# Fri3D_Air_2018_00.net
KiCad netlist of a schematic drawn in Altium Designer
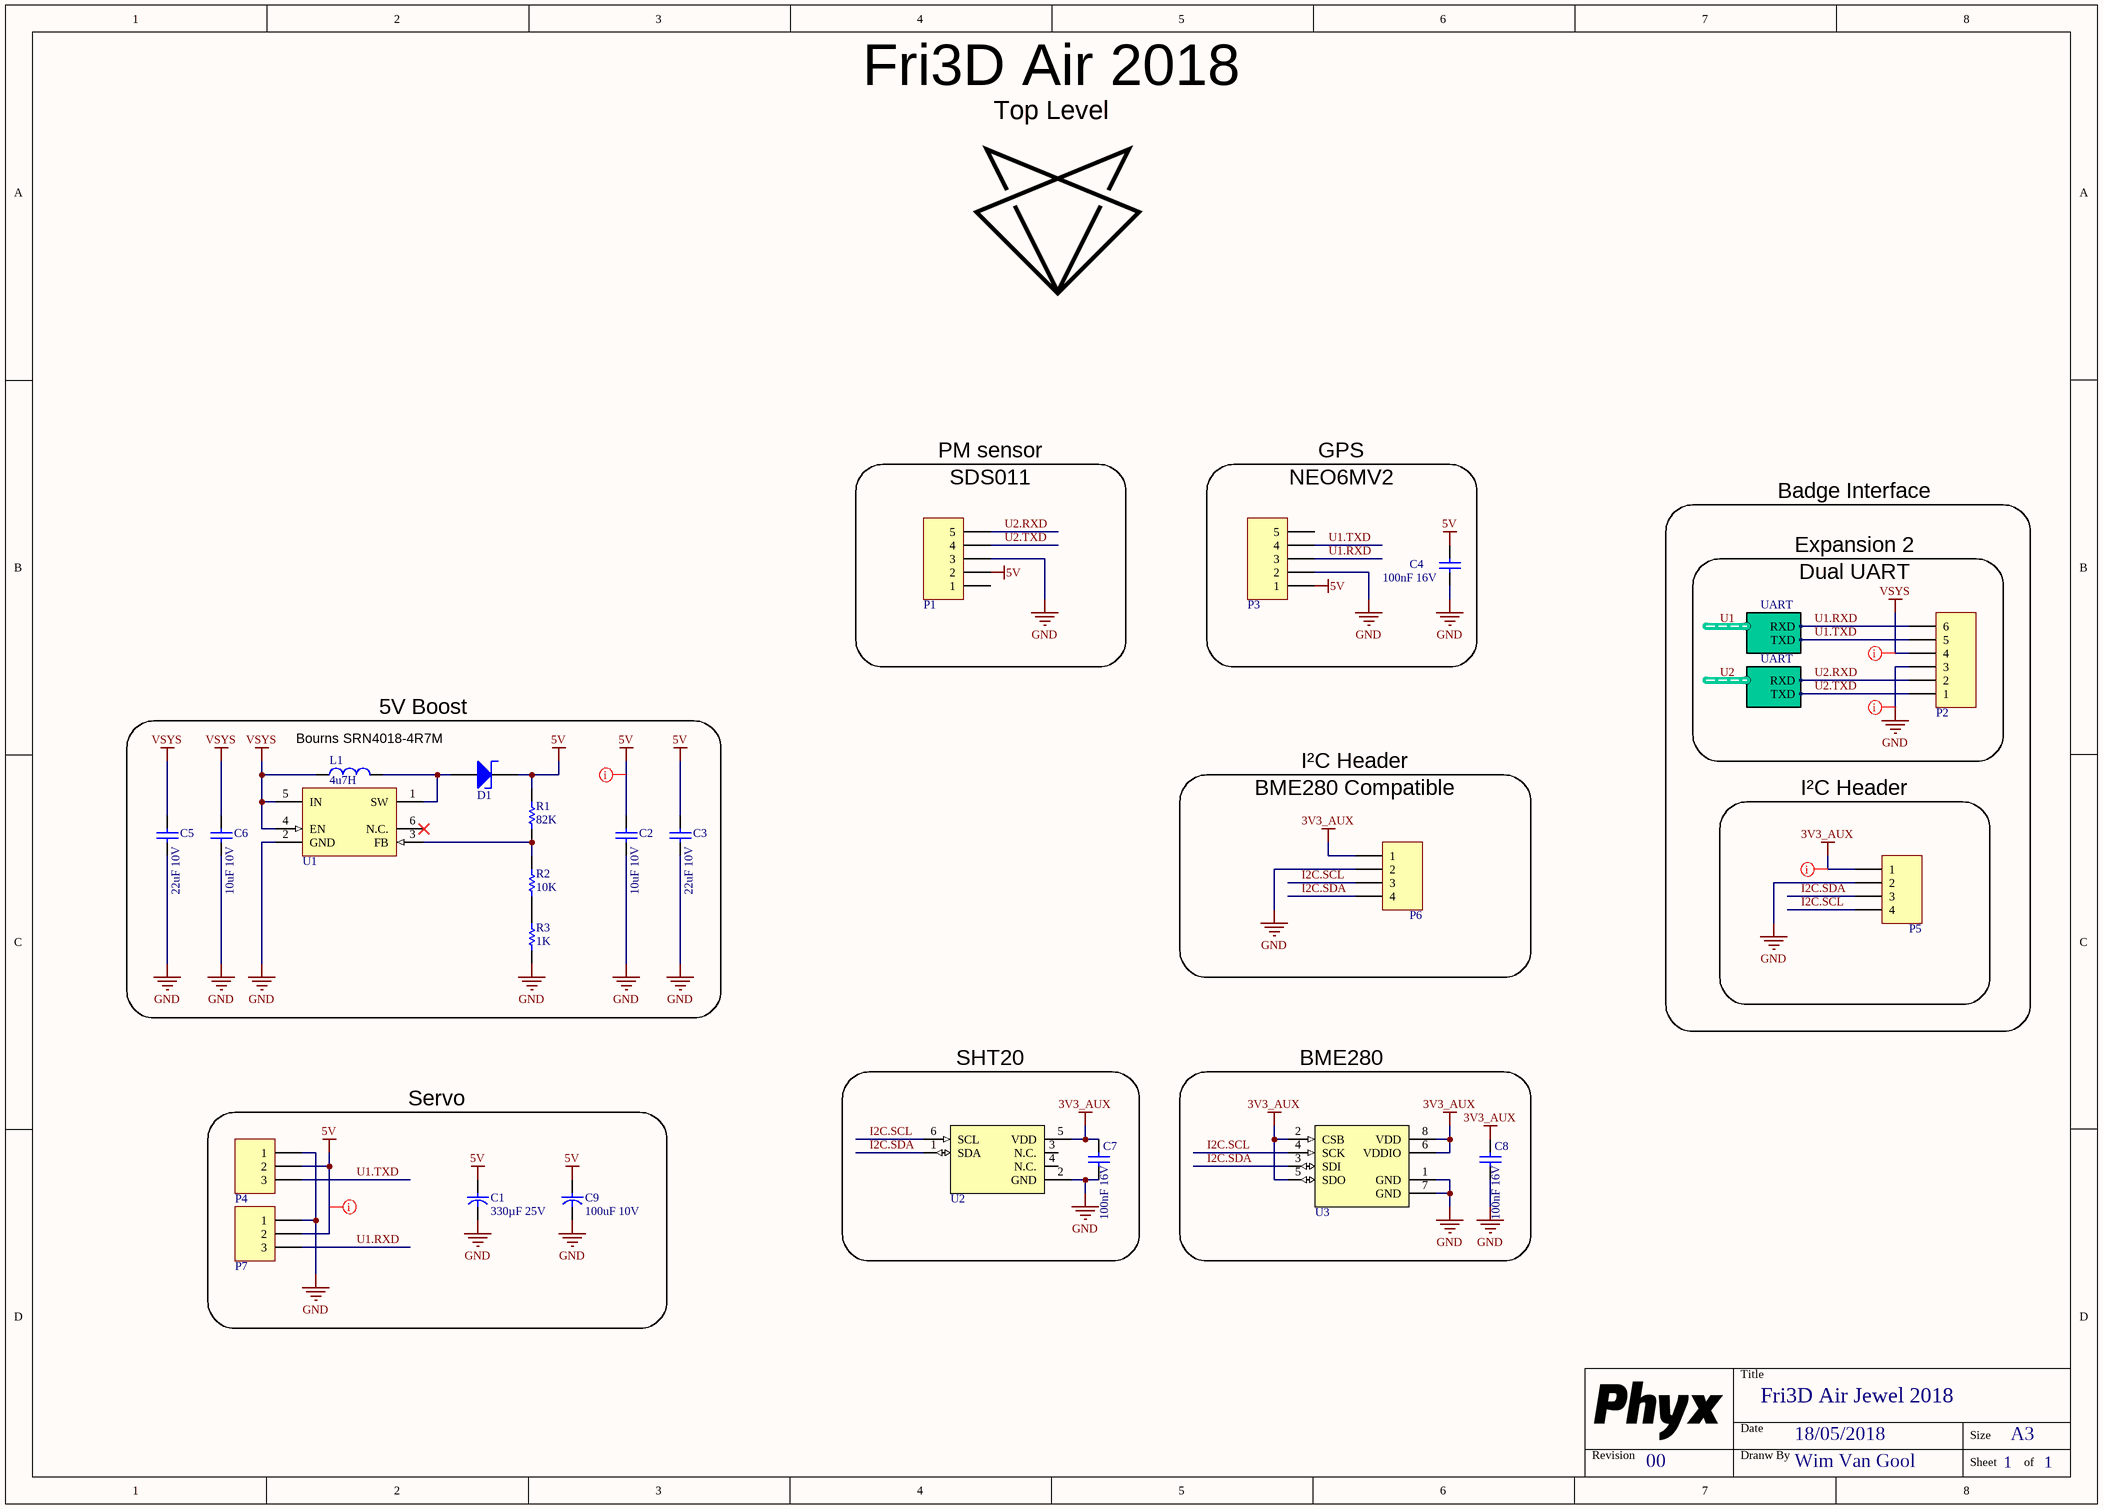
[diagram p0: Fri3D_Air_2018_00.SchDoc]

(export (version "E")
  (design (tool "Eeschema 10.0.6"))
  (components
    (comp (ref "C1")
      (value "330µF 25V")
      (footprint "C_8x15_3.5mm")
      (description "Capacitor electrolyt")
      (fields (field (name "Comment") "CAP_POL"))
      (libsource (lib "Phyx_Components") (part "CAP_POL"))
    )
    (comp (ref "C2")
      (value "10uF 10V")
      (footprint "C0805_N")
      (description "Capacitor Ceramic")
      (fields (field (name "Comment") "CAP_CERAMIC"))
      (libsource (lib "Phyx_Components") (part "CAP_CERAMIC"))
    )
    (comp (ref "C3")
      (value "22uF 10V")
      (footprint "C1210_N")
      (description "Capacitor Ceramic")
      (fields (field (name "Comment") "CAP_CERAMIC"))
      (libsource (lib "Phyx_Components") (part "CAP_CERAMIC"))
    )
    (comp (ref "C4")
      (value "100nF 16V")
      (footprint "C0603_N")
      (description "Capacitor Ceramic")
      (libsource (lib "Phyx_Components") (part "CAP_CERAMIC"))
    )
    (comp (ref "C5")
      (value "22uF 10V")
      (footprint "C1210_N")
      (description "Capacitor Ceramic")
      (fields (field (name "Comment") "CAP_CERAMIC"))
      (libsource (lib "Phyx_Components") (part "CAP_CERAMIC"))
    )
    (comp (ref "C6")
      (value "10uF 10V")
      (footprint "C0805_N")
      (description "Capacitor Ceramic")
      (fields (field (name "Comment") "CAP_CERAMIC"))
      (libsource (lib "Phyx_Components") (part "CAP_CERAMIC"))
    )
    (comp (ref "C7")
      (value "100nF 16V")
      (footprint "C0603_N")
      (description "Capacitor Ceramic")
      (libsource (lib "Phyx_Components") (part "CAP_CERAMIC"))
    )
    (comp (ref "C8")
      (value "100nF 16V")
      (footprint "C0603_N")
      (description "Capacitor Ceramic")
      (libsource (lib "Phyx_Components") (part "CAP_CERAMIC"))
    )
    (comp (ref "C9")
      (value "100uF 10V")
      (footprint "C_5x11_2mm")
      (description "Capacitor electrolyt")
      (fields (field (name "Comment") "CAP_POL"))
      (libsource (lib "Phyx_Components") (part "CAP_POL"))
    )
    (comp (ref "D1")
      (value "NTS260SFT1G  Schottky Rectifier, Single, 60 V, 2 A, SOD-123, 650 mV")
      (footprint "ON_SOD-123FL")
      (description "=Description")
      (libsource (lib "Phyx_Components") (part "Schottky_21"))
    )
    (comp (ref "L1")
      (value "4u7H")
      (footprint "SNL_SWPA4020")
      (fields (field (name "Comment") "SWPA4020S4R7MT"))
      (libsource (lib "Phyx_Components") (part "INDUCTOR"))
    )
    (comp (ref "P1")
      (value "Header 2.5mm RA Shrouded 5")
      (footprint "WE_68800511722")
      (libsource (lib "Phyx_Components") (part "Header 5"))
    )
    (comp (ref "P2")
      (value "Header 6")
      (footprint "HDR1X6")
      (libsource (lib "Phyx_Components") (part "Header 6"))
    )
    (comp (ref "P3")
      (value "Header 5")
      (footprint "HDR1X5")
      (libsource (lib "Phyx_Components") (part "Header 5"))
    )
    (comp (ref "P4")
      (value "Header 3")
      (footprint "HDR1X3")
      (libsource (lib "Phyx_Components") (part "Header 3"))
    )
    (comp (ref "P5")
      (value "Header 4")
      (footprint "HDR1X4")
      (libsource (lib "Phyx_Components") (part "Header 4"))
    )
    (comp (ref "P6")
      (value "Header 4")
      (footprint "HDR1X4")
      (libsource (lib "Phyx_Components") (part "Header 4"))
    )
    (comp (ref "P7")
      (value "Header 3")
      (footprint "HDR1X3")
      (libsource (lib "Phyx_Components") (part "Header 3"))
    )
    (comp (ref "R1")
      (value "82K")
      (footprint "R0603_N")
      (fields (field (name "Comment") "RESISTOR"))
      (libsource (lib "Phyx_Components") (part "RESISTOR"))
    )
    (comp (ref "R2")
      (value "10K")
      (footprint "R0603_N")
      (fields (field (name "Comment") "RESISTOR"))
      (libsource (lib "Phyx_Components") (part "RESISTOR"))
    )
    (comp (ref "R3")
      (value "1K")
      (footprint "R0603_N")
      (fields (field (name "Comment") "RESISTOR"))
      (libsource (lib "Phyx_Components") (part "RESISTOR"))
    )
    (comp (ref "U1")
      (value "High Efficiency 1.2MHz 2A Step Up Converter  SX1308")
      (footprint "SOT23-6")
      (description "=Description")
      (libsource (lib "Phyx_Components") (part "SX1308_Boost"))
    )
    (comp (ref "U2")
      (value "Sensirion SHT20 temperature and humidity sensor I2C")
      (footprint "SNS_DFN6")
      (description "=Description")
      (libsource (lib "Phyx_Components") (part "SHT2x"))
    )
    (comp (ref "U3")
      (value "Bosch BME280 Temperature, humidity, pressure sensor I2C")
      (footprint "BOS_BME280")
      (description "=Description")
      (libsource (lib "Phyx_Components") (part "BOS_BME280"))
    )
  )
  (nets
    (net (code "3") (name "/I2C.SCL") (class "Default")
      (node (ref "P5") (pin "4") (pinfunction "4_4") (pintype "passive"))
      (node (ref "P6") (pin "3") (pinfunction "3_3") (pintype "passive"))
      (node (ref "U2") (pin "6") (pinfunction "SCL_6") (pintype "input"))
      (node (ref "U3") (pin "4") (pinfunction "SCK_4") (pintype "input"))
    )
    (net (code "4") (name "/I2C.SDA") (class "Default")
      (node (ref "P5") (pin "3") (pinfunction "3_3") (pintype "passive"))
      (node (ref "P6") (pin "4") (pinfunction "4_4") (pintype "passive"))
      (node (ref "U2") (pin "1") (pinfunction "SDA_1") (pintype "bidirectional"))
      (node (ref "U3") (pin "3") (pinfunction "SDI_3") (pintype "bidirectional"))
    )
    (net (code "5") (name "/U1.RXD") (class "Default")
      (node (ref "P2") (pin "6") (pinfunction "6_6") (pintype "passive"))
      (node (ref "P3") (pin "3") (pinfunction "3_3") (pintype "passive"))
      (node (ref "P7") (pin "3") (pinfunction "3_3") (pintype "passive"))
    )
    (net (code "6") (name "/U1.TXD") (class "Default")
      (node (ref "P2") (pin "5") (pinfunction "5_5") (pintype "passive"))
      (node (ref "P3") (pin "4") (pinfunction "4_4") (pintype "passive"))
      (node (ref "P4") (pin "3") (pinfunction "3_3") (pintype "passive"))
    )
    (net (code "8") (name "/U2.RXD") (class "Default")
      (node (ref "P1") (pin "5") (pinfunction "5_5") (pintype "passive"))
      (node (ref "P2") (pin "2") (pinfunction "2_2") (pintype "passive"))
    )
    (net (code "9") (name "/U2.TXD") (class "Default")
      (node (ref "P1") (pin "4") (pinfunction "4_4") (pintype "passive"))
      (node (ref "P2") (pin "1") (pinfunction "1_1") (pintype "passive"))
    )
    (net (code "11") (name "3V3_AUX") (class "Default")
      (node (ref "C7") (pin "1") (pinfunction "1_1") (pintype "passive"))
      (node (ref "C8") (pin "1") (pinfunction "1_1") (pintype "passive"))
      (node (ref "P5") (pin "1") (pinfunction "1_1") (pintype "passive"))
      (node (ref "P6") (pin "1") (pinfunction "1_1") (pintype "passive"))
      (node (ref "U2") (pin "5") (pinfunction "VDD_5") (pintype "power_in"))
      (node (ref "U3") (pin "2") (pinfunction "CSB_2") (pintype "input"))
      (node (ref "U3") (pin "5") (pinfunction "SDO_5") (pintype "bidirectional"))
      (node (ref "U3") (pin "6") (pinfunction "VDDIO_6") (pintype "power_in"))
      (node (ref "U3") (pin "8") (pinfunction "VDD_8") (pintype "power_in"))
    )
    (net (code "12") (name "5V") (class "Default")
      (node (ref "C1") (pin "1") (pinfunction "1_1") (pintype "passive"))
      (node (ref "C2") (pin "1") (pinfunction "1_1") (pintype "passive"))
      (node (ref "C3") (pin "1") (pinfunction "1_1") (pintype "passive"))
      (node (ref "C4") (pin "1") (pinfunction "1_1") (pintype "passive"))
      (node (ref "C9") (pin "1") (pinfunction "1_1") (pintype "passive"))
      (node (ref "D1") (pin "1") (pinfunction "C_1") (pintype "passive"))
      (node (ref "P1") (pin "2") (pinfunction "2_2") (pintype "passive"))
      (node (ref "P3") (pin "1") (pinfunction "1_1") (pintype "passive"))
      (node (ref "P4") (pin "2") (pinfunction "2_2") (pintype "passive"))
      (node (ref "P7") (pin "2") (pinfunction "2_2") (pintype "passive"))
      (node (ref "R1") (pin "1") (pinfunction "1_1") (pintype "passive"))
    )
    (net (code "13") (name "GND") (class "Default")
      (node (ref "C1") (pin "2") (pinfunction "2_2") (pintype "passive"))
      (node (ref "C2") (pin "2") (pinfunction "2_2") (pintype "passive"))
      (node (ref "C3") (pin "2") (pinfunction "2_2") (pintype "passive"))
      (node (ref "C4") (pin "2") (pinfunction "2_2") (pintype "passive"))
      (node (ref "C5") (pin "2") (pinfunction "2_2") (pintype "passive"))
      (node (ref "C6") (pin "2") (pinfunction "2_2") (pintype "passive"))
      (node (ref "C7") (pin "2") (pinfunction "2_2") (pintype "passive"))
      (node (ref "C8") (pin "2") (pinfunction "2_2") (pintype "passive"))
      (node (ref "C9") (pin "2") (pinfunction "2_2") (pintype "passive"))
      (node (ref "P1") (pin "3") (pinfunction "3_3") (pintype "passive"))
      (node (ref "P2") (pin "3") (pinfunction "3_3") (pintype "passive"))
      (node (ref "P3") (pin "2") (pinfunction "2_2") (pintype "passive"))
      (node (ref "P4") (pin "1") (pinfunction "1_1") (pintype "passive"))
      (node (ref "P5") (pin "2") (pinfunction "2_2") (pintype "passive"))
      (node (ref "P6") (pin "2") (pinfunction "2_2") (pintype "passive"))
      (node (ref "P7") (pin "1") (pinfunction "1_1") (pintype "passive"))
      (node (ref "R3") (pin "2") (pinfunction "2_2") (pintype "passive"))
      (node (ref "U1") (pin "2") (pinfunction "GND_2") (pintype "power_in"))
      (node (ref "U2") (pin "2") (pinfunction "GND_2") (pintype "power_in"))
      (node (ref "U3") (pin "1") (pinfunction "GND_1") (pintype "power_in"))
      (node (ref "U3") (pin "7") (pinfunction "GND_7") (pintype "power_in"))
    )
    (net (code "14") (name "Net-(D1-A)") (class "Default")
      (node (ref "D1") (pin "2") (pinfunction "A_2") (pintype "passive"))
      (node (ref "L1") (pin "2") (pinfunction "2_2") (pintype "passive"))
      (node (ref "U1") (pin "1") (pinfunction "SW_1") (pintype "power_in"))
    )
    (net (code "15") (name "Net-(R2-Pad2)") (class "Default")
      (node (ref "R2") (pin "2") (pinfunction "2_2") (pintype "passive"))
      (node (ref "R3") (pin "1") (pinfunction "1_1") (pintype "passive"))
    )
    (net (code "16") (name "Net-(U1-FB)") (class "Default")
      (node (ref "R1") (pin "2") (pinfunction "2_2") (pintype "passive"))
      (node (ref "R2") (pin "1") (pinfunction "1_1") (pintype "passive"))
      (node (ref "U1") (pin "3") (pinfunction "FB_3") (pintype "input"))
    )
    (net (code "17") (name "VSYS") (class "Default")
      (node (ref "C5") (pin "1") (pinfunction "1_1") (pintype "passive"))
      (node (ref "C6") (pin "1") (pinfunction "1_1") (pintype "passive"))
      (node (ref "L1") (pin "1") (pinfunction "1_1") (pintype "passive"))
      (node (ref "P2") (pin "4") (pinfunction "4_4") (pintype "passive"))
      (node (ref "U1") (pin "4") (pinfunction "EN_4") (pintype "input"))
      (node (ref "U1") (pin "5") (pinfunction "IN_5") (pintype "power_in"))
    )
    (net (code "18") (name "unconnected-(P1-Pad1)") (class "Default")
      (node (ref "P1") (pin "1") (pinfunction "1_1") (pintype "passive"))
    )
    (net (code "19") (name "unconnected-(P3-Pad5)") (class "Default")
      (node (ref "P3") (pin "5") (pinfunction "5_5") (pintype "passive"))
    )
    (net (code "20") (name "unconnected-(U1-N.C.-Pad6)") (class "Default")
      (node (ref "U1") (pin "6") (pinfunction "N.C._6") (pintype "power_in+no_connect"))
    )
    (net (code "21") (name "unconnected-(U2-N.C.-Pad3)") (class "Default")
      (node (ref "U2") (pin "3") (pinfunction "N.C._3") (pintype "passive"))
    )
    (net (code "22") (name "unconnected-(U2-N.C.-Pad4)") (class "Default")
      (node (ref "U2") (pin "4") (pinfunction "N.C._4") (pintype "passive"))
    )
  )
)
